# DisplayBoard.net
KiCad netlist of a schematic drawn in EAGLE
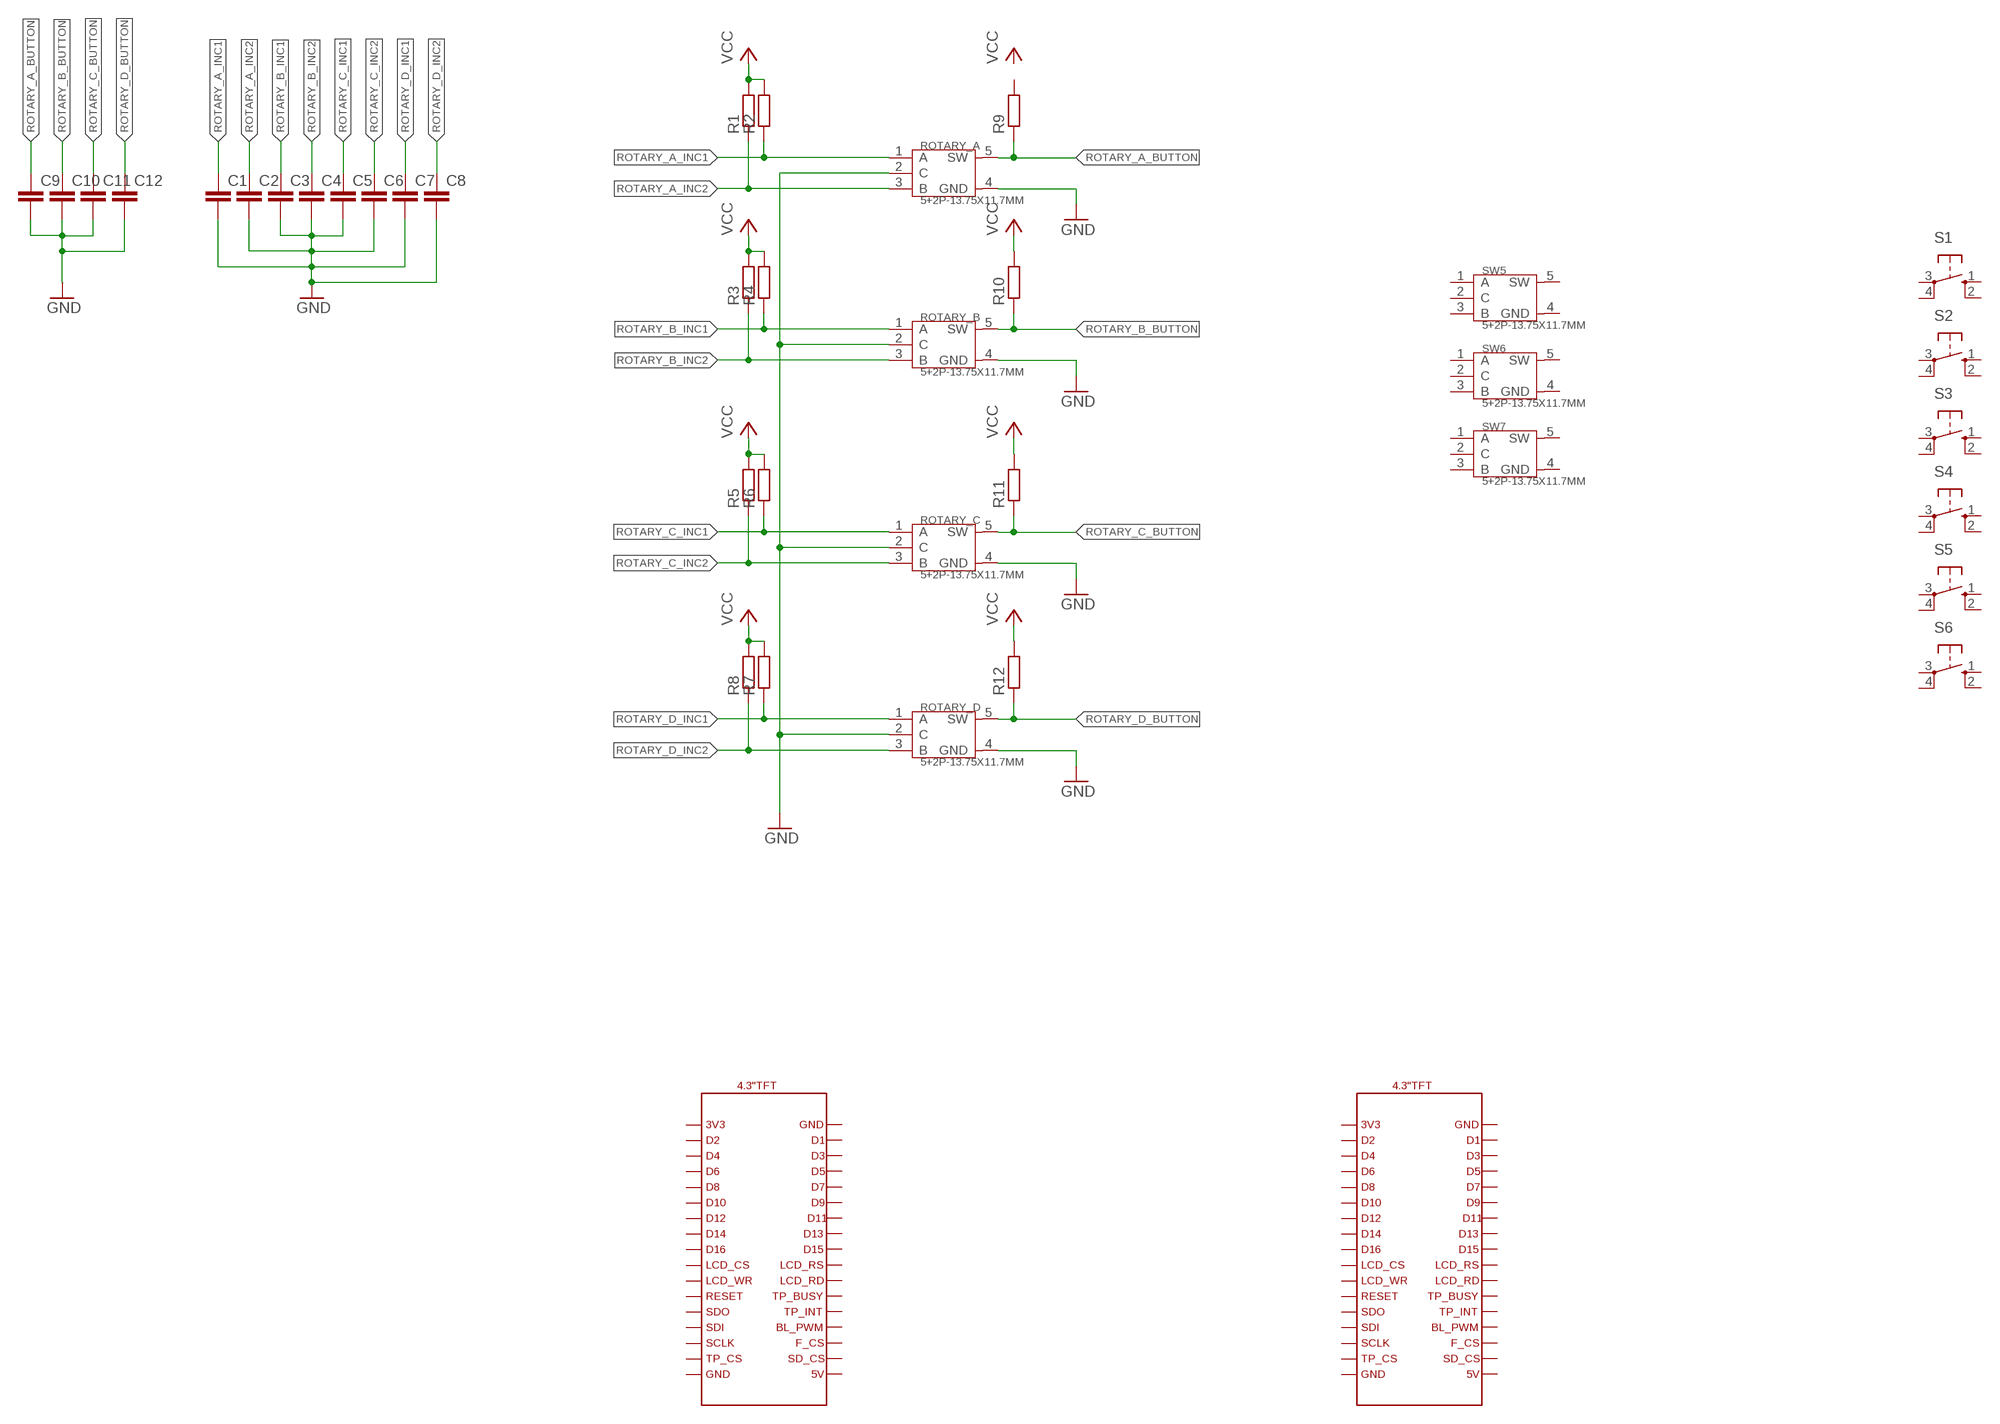
[diagram p0: schematic, sheet 1]

(export (version "E")
  (design (tool "Eeschema 10.0.6"))
  (components
    (comp (ref "C1")
      (value "C-EUC0805")
      (footprint "eagle-import:C0805")
      (libsource (lib "eagle-import") (part "C-EUC0805"))
    )
    (comp (ref "C2")
      (value "C-EUC0805")
      (footprint "eagle-import:C0805")
      (libsource (lib "eagle-import") (part "C-EUC0805"))
    )
    (comp (ref "C3")
      (value "C-EUC0805")
      (footprint "eagle-import:C0805")
      (libsource (lib "eagle-import") (part "C-EUC0805"))
    )
    (comp (ref "C4")
      (value "C-EUC0805")
      (footprint "eagle-import:C0805")
      (libsource (lib "eagle-import") (part "C-EUC0805"))
    )
    (comp (ref "C5")
      (value "C-EUC0805")
      (footprint "eagle-import:C0805")
      (libsource (lib "eagle-import") (part "C-EUC0805"))
    )
    (comp (ref "C6")
      (value "C-EUC0805")
      (footprint "eagle-import:C0805")
      (libsource (lib "eagle-import") (part "C-EUC0805"))
    )
    (comp (ref "C7")
      (value "C-EUC0805")
      (footprint "eagle-import:C0805")
      (libsource (lib "eagle-import") (part "C-EUC0805"))
    )
    (comp (ref "C8")
      (value "C-EUC0805")
      (footprint "eagle-import:C0805")
      (libsource (lib "eagle-import") (part "C-EUC0805"))
    )
    (comp (ref "C9")
      (value "C-EUC0805")
      (footprint "eagle-import:C0805")
      (libsource (lib "eagle-import") (part "C-EUC0805"))
    )
    (comp (ref "C10")
      (value "C-EUC0805")
      (footprint "eagle-import:C0805")
      (libsource (lib "eagle-import") (part "C-EUC0805"))
    )
    (comp (ref "C11")
      (value "C-EUC0805")
      (footprint "eagle-import:C0805")
      (libsource (lib "eagle-import") (part "C-EUC0805"))
    )
    (comp (ref "C12")
      (value "C-EUC0805")
      (footprint "eagle-import:C0805")
      (libsource (lib "eagle-import") (part "C-EUC0805"))
    )
    (comp (ref "R1")
      (value "R-EU_R0805")
      (footprint "eagle-import:R0805")
      (libsource (lib "eagle-import") (part "R-EU_R0805"))
    )
    (comp (ref "R2")
      (value "R-EU_R0805")
      (footprint "eagle-import:R0805")
      (libsource (lib "eagle-import") (part "R-EU_R0805"))
    )
    (comp (ref "R3")
      (value "R-EU_R0805")
      (footprint "eagle-import:R0805")
      (libsource (lib "eagle-import") (part "R-EU_R0805"))
    )
    (comp (ref "R4")
      (value "R-EU_R0805")
      (footprint "eagle-import:R0805")
      (libsource (lib "eagle-import") (part "R-EU_R0805"))
    )
    (comp (ref "R5")
      (value "R-EU_R0805")
      (footprint "eagle-import:R0805")
      (libsource (lib "eagle-import") (part "R-EU_R0805"))
    )
    (comp (ref "R6")
      (value "R-EU_R0805")
      (footprint "eagle-import:R0805")
      (libsource (lib "eagle-import") (part "R-EU_R0805"))
    )
    (comp (ref "R7")
      (value "R-EU_R0805")
      (footprint "eagle-import:R0805")
      (libsource (lib "eagle-import") (part "R-EU_R0805"))
    )
    (comp (ref "R8")
      (value "R-EU_R0805")
      (footprint "eagle-import:R0805")
      (libsource (lib "eagle-import") (part "R-EU_R0805"))
    )
    (comp (ref "R9")
      (value "R-EU_R0805")
      (footprint "eagle-import:R0805")
      (libsource (lib "eagle-import") (part "R-EU_R0805"))
    )
    (comp (ref "R10")
      (value "R-EU_R0805")
      (footprint "eagle-import:R0805")
      (libsource (lib "eagle-import") (part "R-EU_R0805"))
    )
    (comp (ref "R11")
      (value "R-EU_R0805")
      (footprint "eagle-import:R0805")
      (libsource (lib "eagle-import") (part "R-EU_R0805"))
    )
    (comp (ref "R12")
      (value "R-EU_R0805")
      (footprint "eagle-import:R0805")
      (libsource (lib "eagle-import") (part "R-EU_R0805"))
    )
    (comp (ref "ROTARY_A")
      (value "5+2P-13.75X11.7MM")
      (footprint "eagle-import:SW7-13.75X11.7X6.5MM")
      (fields (field (name "MPN") "Rotary-switch"))
      (libsource (lib "eagle-import") (part "DIP-ROTARY-SWITCH(5+2P-13.75X11.7MM)"))
    )
    (comp (ref "ROTARY_B")
      (value "5+2P-13.75X11.7MM")
      (footprint "eagle-import:SW7-13.75X11.7X6.5MM")
      (fields (field (name "MPN") "Rotary-switch"))
      (libsource (lib "eagle-import") (part "DIP-ROTARY-SWITCH(5+2P-13.75X11.7MM)"))
    )
    (comp (ref "ROTARY_C")
      (value "5+2P-13.75X11.7MM")
      (footprint "eagle-import:SW7-13.75X11.7X6.5MM")
      (fields (field (name "MPN") "Rotary-switch"))
      (libsource (lib "eagle-import") (part "DIP-ROTARY-SWITCH(5+2P-13.75X11.7MM)"))
    )
    (comp (ref "ROTARY_D")
      (value "5+2P-13.75X11.7MM")
      (footprint "eagle-import:SW7-13.75X11.7X6.5MM")
      (fields (field (name "MPN") "Rotary-switch"))
      (libsource (lib "eagle-import") (part "DIP-ROTARY-SWITCH(5+2P-13.75X11.7MM)"))
    )
    (comp (ref "S1")
      (value "10-XX")
      (footprint "eagle-import:B3F-10XX")
      (fields (field (name "MPN") "B3F-1000"))
      (libsource (lib "eagle-import") (part "10-XX"))
    )
    (comp (ref "S2")
      (value "10-XX")
      (footprint "eagle-import:B3F-10XX")
      (fields (field (name "MPN") "B3F-1000"))
      (libsource (lib "eagle-import") (part "10-XX"))
    )
    (comp (ref "S3")
      (value "10-XX")
      (footprint "eagle-import:B3F-10XX")
      (fields (field (name "MPN") "B3F-1000"))
      (libsource (lib "eagle-import") (part "10-XX"))
    )
    (comp (ref "S4")
      (value "10-XX")
      (footprint "eagle-import:B3F-10XX")
      (fields (field (name "MPN") "B3F-1000"))
      (libsource (lib "eagle-import") (part "10-XX"))
    )
    (comp (ref "S5")
      (value "10-XX")
      (footprint "eagle-import:B3F-10XX")
      (fields (field (name "MPN") "B3F-1000"))
      (libsource (lib "eagle-import") (part "10-XX"))
    )
    (comp (ref "S6")
      (value "10-XX")
      (footprint "eagle-import:B3F-10XX")
      (fields (field (name "MPN") "B3F-1000"))
      (libsource (lib "eagle-import") (part "10-XX"))
    )
    (comp (ref "SW5")
      (value "5+2P-13.75X11.7MM")
      (footprint "eagle-import:SW7-13.75X11.7X6.5MM")
      (fields (field (name "MPN") "Rotary-switch"))
      (libsource (lib "eagle-import") (part "DIP-ROTARY-SWITCH(5+2P-13.75X11.7MM)"))
    )
    (comp (ref "SW6")
      (value "5+2P-13.75X11.7MM")
      (footprint "eagle-import:SW7-13.75X11.7X6.5MM")
      (fields (field (name "MPN") "Rotary-switch"))
      (libsource (lib "eagle-import") (part "DIP-ROTARY-SWITCH(5+2P-13.75X11.7MM)"))
    )
    (comp (ref "SW7")
      (value "5+2P-13.75X11.7MM")
      (footprint "eagle-import:SW7-13.75X11.7X6.5MM")
      (fields (field (name "MPN") "Rotary-switch"))
      (libsource (lib "eagle-import") (part "DIP-ROTARY-SWITCH(5+2P-13.75X11.7MM)"))
    )
    (comp (ref "U$1")
      (value "4.3\"TFT")
      (footprint "eagle-import:4.3TFT")
      (libsource (lib "eagle-import") (part "4.3{dblquote}TFT"))
    )
  )
  (nets
    (net (code "1") (name "GND") (class "Default")
      (node (ref "C1") (pin "2") (pinfunction "2_2") (pintype "passive"))
      (node (ref "C10") (pin "2") (pinfunction "2_2") (pintype "passive"))
      (node (ref "C11") (pin "2") (pinfunction "2_2") (pintype "passive"))
      (node (ref "C12") (pin "2") (pinfunction "2_2") (pintype "passive"))
      (node (ref "C2") (pin "2") (pinfunction "2_2") (pintype "passive"))
      (node (ref "C3") (pin "2") (pinfunction "2_2") (pintype "passive"))
      (node (ref "C4") (pin "2") (pinfunction "2_2") (pintype "passive"))
      (node (ref "C5") (pin "2") (pinfunction "2_2") (pintype "passive"))
      (node (ref "C6") (pin "2") (pinfunction "2_2") (pintype "passive"))
      (node (ref "C7") (pin "2") (pinfunction "2_2") (pintype "passive"))
      (node (ref "C8") (pin "2") (pinfunction "2_2") (pintype "passive"))
      (node (ref "C9") (pin "2") (pinfunction "2_2") (pintype "passive"))
      (node (ref "ROTARY_A") (pin "2") (pinfunction "C_2") (pintype "bidirectional"))
      (node (ref "ROTARY_A") (pin "4") (pinfunction "GND_4") (pintype "bidirectional"))
      (node (ref "ROTARY_B") (pin "2") (pinfunction "C_2") (pintype "bidirectional"))
      (node (ref "ROTARY_B") (pin "4") (pinfunction "GND_4") (pintype "bidirectional"))
      (node (ref "ROTARY_C") (pin "2") (pinfunction "C_2") (pintype "bidirectional"))
      (node (ref "ROTARY_C") (pin "4") (pinfunction "GND_4") (pintype "bidirectional"))
      (node (ref "ROTARY_D") (pin "2") (pinfunction "C_2") (pintype "bidirectional"))
      (node (ref "ROTARY_D") (pin "4") (pinfunction "GND_4") (pintype "bidirectional"))
    )
    (net (code "2") (name "ROTARY_A_BUTTON") (class "Default")
      (node (ref "C9") (pin "1") (pinfunction "1_1") (pintype "passive"))
      (node (ref "R9") (pin "1") (pinfunction "1_1") (pintype "passive"))
      (node (ref "ROTARY_A") (pin "5") (pinfunction "SW_5") (pintype "bidirectional"))
    )
    (net (code "3") (name "ROTARY_A_INC1") (class "Default")
      (node (ref "C1") (pin "1") (pinfunction "1_1") (pintype "passive"))
      (node (ref "R2") (pin "1") (pinfunction "1_1") (pintype "passive"))
      (node (ref "ROTARY_A") (pin "1") (pinfunction "A_1") (pintype "bidirectional"))
    )
    (net (code "4") (name "ROTARY_A_INC2") (class "Default")
      (node (ref "C2") (pin "1") (pinfunction "1_1") (pintype "passive"))
      (node (ref "R1") (pin "1") (pinfunction "1_1") (pintype "passive"))
      (node (ref "ROTARY_A") (pin "3") (pinfunction "B_3") (pintype "bidirectional"))
    )
    (net (code "5") (name "ROTARY_B_BUTTON") (class "Default")
      (node (ref "C10") (pin "1") (pinfunction "1_1") (pintype "passive"))
      (node (ref "R10") (pin "1") (pinfunction "1_1") (pintype "passive"))
      (node (ref "ROTARY_B") (pin "5") (pinfunction "SW_5") (pintype "bidirectional"))
    )
    (net (code "6") (name "ROTARY_B_INC1") (class "Default")
      (node (ref "C3") (pin "1") (pinfunction "1_1") (pintype "passive"))
      (node (ref "R4") (pin "1") (pinfunction "1_1") (pintype "passive"))
      (node (ref "ROTARY_B") (pin "1") (pinfunction "A_1") (pintype "bidirectional"))
    )
    (net (code "7") (name "ROTARY_B_INC2") (class "Default")
      (node (ref "C4") (pin "1") (pinfunction "1_1") (pintype "passive"))
      (node (ref "R3") (pin "1") (pinfunction "1_1") (pintype "passive"))
      (node (ref "ROTARY_B") (pin "3") (pinfunction "B_3") (pintype "bidirectional"))
    )
    (net (code "8") (name "ROTARY_C_BUTTON") (class "Default")
      (node (ref "C11") (pin "1") (pinfunction "1_1") (pintype "passive"))
      (node (ref "R11") (pin "1") (pinfunction "1_1") (pintype "passive"))
      (node (ref "ROTARY_C") (pin "5") (pinfunction "SW_5") (pintype "bidirectional"))
    )
    (net (code "9") (name "ROTARY_C_INC1") (class "Default")
      (node (ref "C5") (pin "1") (pinfunction "1_1") (pintype "passive"))
      (node (ref "R6") (pin "1") (pinfunction "1_1") (pintype "passive"))
      (node (ref "ROTARY_C") (pin "1") (pinfunction "A_1") (pintype "bidirectional"))
    )
    (net (code "10") (name "ROTARY_C_INC2") (class "Default")
      (node (ref "C6") (pin "1") (pinfunction "1_1") (pintype "passive"))
      (node (ref "R5") (pin "1") (pinfunction "1_1") (pintype "passive"))
      (node (ref "ROTARY_C") (pin "3") (pinfunction "B_3") (pintype "bidirectional"))
    )
    (net (code "11") (name "ROTARY_D_BUTTON") (class "Default")
      (node (ref "C12") (pin "1") (pinfunction "1_1") (pintype "passive"))
      (node (ref "R12") (pin "1") (pinfunction "1_1") (pintype "passive"))
      (node (ref "ROTARY_D") (pin "5") (pinfunction "SW_5") (pintype "bidirectional"))
    )
    (net (code "12") (name "ROTARY_D_INC1") (class "Default")
      (node (ref "C7") (pin "1") (pinfunction "1_1") (pintype "passive"))
      (node (ref "R7") (pin "1") (pinfunction "1_1") (pintype "passive"))
      (node (ref "ROTARY_D") (pin "1") (pinfunction "A_1") (pintype "bidirectional"))
    )
    (net (code "13") (name "ROTARY_D_INC2") (class "Default")
      (node (ref "C8") (pin "1") (pinfunction "1_1") (pintype "passive"))
      (node (ref "R8") (pin "1") (pinfunction "1_1") (pintype "passive"))
      (node (ref "ROTARY_D") (pin "3") (pinfunction "B_3") (pintype "bidirectional"))
    )
    (net (code "14") (name "VCC") (class "Default")
      (node (ref "R1") (pin "2") (pinfunction "2_2") (pintype "passive"))
      (node (ref "R10") (pin "2") (pinfunction "2_2") (pintype "passive"))
      (node (ref "R11") (pin "2") (pinfunction "2_2") (pintype "passive"))
      (node (ref "R12") (pin "2") (pinfunction "2_2") (pintype "passive"))
      (node (ref "R2") (pin "2") (pinfunction "2_2") (pintype "passive"))
      (node (ref "R3") (pin "2") (pinfunction "2_2") (pintype "passive"))
      (node (ref "R4") (pin "2") (pinfunction "2_2") (pintype "passive"))
      (node (ref "R5") (pin "2") (pinfunction "2_2") (pintype "passive"))
      (node (ref "R6") (pin "2") (pinfunction "2_2") (pintype "passive"))
      (node (ref "R7") (pin "2") (pinfunction "2_2") (pintype "passive"))
      (node (ref "R8") (pin "2") (pinfunction "2_2") (pintype "passive"))
    )
    (net (code "15") (name "unconnected-(R9-Pad2)") (class "Default")
      (node (ref "R9") (pin "2") (pinfunction "2_2") (pintype "passive"))
    )
    (net (code "16") (name "unconnected-(S1-P-Pad3)") (class "Default")
      (node (ref "S1") (pin "3") (pinfunction "P_3") (pintype "passive"))
    )
    (net (code "17") (name "unconnected-(S1-P1-Pad4)") (class "Default")
      (node (ref "S1") (pin "4") (pinfunction "P1_4") (pintype "passive"))
    )
    (net (code "18") (name "unconnected-(S1-S-Pad1)") (class "Default")
      (node (ref "S1") (pin "1") (pinfunction "S_1") (pintype "passive"))
    )
    (net (code "19") (name "unconnected-(S1-S1-Pad2)") (class "Default")
      (node (ref "S1") (pin "2") (pinfunction "S1_2") (pintype "passive"))
    )
    (net (code "20") (name "unconnected-(S2-P-Pad3)") (class "Default")
      (node (ref "S2") (pin "3") (pinfunction "P_3") (pintype "passive"))
    )
    (net (code "21") (name "unconnected-(S2-P1-Pad4)") (class "Default")
      (node (ref "S2") (pin "4") (pinfunction "P1_4") (pintype "passive"))
    )
    (net (code "22") (name "unconnected-(S2-S-Pad1)") (class "Default")
      (node (ref "S2") (pin "1") (pinfunction "S_1") (pintype "passive"))
    )
    (net (code "23") (name "unconnected-(S2-S1-Pad2)") (class "Default")
      (node (ref "S2") (pin "2") (pinfunction "S1_2") (pintype "passive"))
    )
    (net (code "24") (name "unconnected-(S3-P-Pad3)") (class "Default")
      (node (ref "S3") (pin "3") (pinfunction "P_3") (pintype "passive"))
    )
    (net (code "25") (name "unconnected-(S3-P1-Pad4)") (class "Default")
      (node (ref "S3") (pin "4") (pinfunction "P1_4") (pintype "passive"))
    )
    (net (code "26") (name "unconnected-(S3-S-Pad1)") (class "Default")
      (node (ref "S3") (pin "1") (pinfunction "S_1") (pintype "passive"))
    )
    (net (code "27") (name "unconnected-(S3-S1-Pad2)") (class "Default")
      (node (ref "S3") (pin "2") (pinfunction "S1_2") (pintype "passive"))
    )
    (net (code "28") (name "unconnected-(S4-P-Pad3)") (class "Default")
      (node (ref "S4") (pin "3") (pinfunction "P_3") (pintype "passive"))
    )
    (net (code "29") (name "unconnected-(S4-P1-Pad4)") (class "Default")
      (node (ref "S4") (pin "4") (pinfunction "P1_4") (pintype "passive"))
    )
    (net (code "30") (name "unconnected-(S4-S-Pad1)") (class "Default")
      (node (ref "S4") (pin "1") (pinfunction "S_1") (pintype "passive"))
    )
    (net (code "31") (name "unconnected-(S4-S1-Pad2)") (class "Default")
      (node (ref "S4") (pin "2") (pinfunction "S1_2") (pintype "passive"))
    )
    (net (code "32") (name "unconnected-(S5-P-Pad3)") (class "Default")
      (node (ref "S5") (pin "3") (pinfunction "P_3") (pintype "passive"))
    )
    (net (code "33") (name "unconnected-(S5-P1-Pad4)") (class "Default")
      (node (ref "S5") (pin "4") (pinfunction "P1_4") (pintype "passive"))
    )
    (net (code "34") (name "unconnected-(S5-S-Pad1)") (class "Default")
      (node (ref "S5") (pin "1") (pinfunction "S_1") (pintype "passive"))
    )
    (net (code "35") (name "unconnected-(S5-S1-Pad2)") (class "Default")
      (node (ref "S5") (pin "2") (pinfunction "S1_2") (pintype "passive"))
    )
    (net (code "36") (name "unconnected-(S6-P-Pad3)") (class "Default")
      (node (ref "S6") (pin "3") (pinfunction "P_3") (pintype "passive"))
    )
    (net (code "37") (name "unconnected-(S6-P1-Pad4)") (class "Default")
      (node (ref "S6") (pin "4") (pinfunction "P1_4") (pintype "passive"))
    )
    (net (code "38") (name "unconnected-(S6-S-Pad1)") (class "Default")
      (node (ref "S6") (pin "1") (pinfunction "S_1") (pintype "passive"))
    )
    (net (code "39") (name "unconnected-(S6-S1-Pad2)") (class "Default")
      (node (ref "S6") (pin "2") (pinfunction "S1_2") (pintype "passive"))
    )
    (net (code "40") (name "unconnected-(SW5-A-Pad1)") (class "Default")
      (node (ref "SW5") (pin "1") (pinfunction "A_1") (pintype "bidirectional"))
    )
    (net (code "41") (name "unconnected-(SW5-B-Pad3)") (class "Default")
      (node (ref "SW5") (pin "3") (pinfunction "B_3") (pintype "bidirectional"))
    )
    (net (code "42") (name "unconnected-(SW5-C-Pad2)") (class "Default")
      (node (ref "SW5") (pin "2") (pinfunction "C_2") (pintype "bidirectional"))
    )
    (net (code "43") (name "unconnected-(SW5-GND-Pad4)") (class "Default")
      (node (ref "SW5") (pin "4") (pinfunction "GND_4") (pintype "bidirectional"))
    )
    (net (code "44") (name "unconnected-(SW5-SW-Pad5)") (class "Default")
      (node (ref "SW5") (pin "5") (pinfunction "SW_5") (pintype "bidirectional"))
    )
    (net (code "45") (name "unconnected-(SW6-A-Pad1)") (class "Default")
      (node (ref "SW6") (pin "1") (pinfunction "A_1") (pintype "bidirectional"))
    )
    (net (code "46") (name "unconnected-(SW6-B-Pad3)") (class "Default")
      (node (ref "SW6") (pin "3") (pinfunction "B_3") (pintype "bidirectional"))
    )
    (net (code "47") (name "unconnected-(SW6-C-Pad2)") (class "Default")
      (node (ref "SW6") (pin "2") (pinfunction "C_2") (pintype "bidirectional"))
    )
    (net (code "48") (name "unconnected-(SW6-GND-Pad4)") (class "Default")
      (node (ref "SW6") (pin "4") (pinfunction "GND_4") (pintype "bidirectional"))
    )
    (net (code "49") (name "unconnected-(SW6-SW-Pad5)") (class "Default")
      (node (ref "SW6") (pin "5") (pinfunction "SW_5") (pintype "bidirectional"))
    )
    (net (code "50") (name "unconnected-(SW7-A-Pad1)") (class "Default")
      (node (ref "SW7") (pin "1") (pinfunction "A_1") (pintype "bidirectional"))
    )
    (net (code "51") (name "unconnected-(SW7-B-Pad3)") (class "Default")
      (node (ref "SW7") (pin "3") (pinfunction "B_3") (pintype "bidirectional"))
    )
    (net (code "52") (name "unconnected-(SW7-C-Pad2)") (class "Default")
      (node (ref "SW7") (pin "2") (pinfunction "C_2") (pintype "bidirectional"))
    )
    (net (code "53") (name "unconnected-(SW7-GND-Pad4)") (class "Default")
      (node (ref "SW7") (pin "4") (pinfunction "GND_4") (pintype "bidirectional"))
    )
    (net (code "54") (name "unconnected-(SW7-SW-Pad5)") (class "Default")
      (node (ref "SW7") (pin "5") (pinfunction "SW_5") (pintype "bidirectional"))
    )
    (net (code "55") (name "unconnected-(U$1A-P$1-PadJP1_1)") (class "Default")
      (node (ref "U$1") (pin "JP1_1") (pinfunction "P$1_JP1_1") (pintype "bidirectional"))
    )
    (net (code "56") (name "unconnected-(U$1A-P$2-PadJP1_2)") (class "Default")
      (node (ref "U$1") (pin "JP1_2") (pinfunction "P$2_JP1_2") (pintype "bidirectional"))
    )
    (net (code "57") (name "unconnected-(U$1A-P$3-PadJP1_3)") (class "Default")
      (node (ref "U$1") (pin "JP1_3") (pinfunction "P$3_JP1_3") (pintype "bidirectional"))
    )
    (net (code "58") (name "unconnected-(U$1A-P$4-PadJP1_4)") (class "Default")
      (node (ref "U$1") (pin "JP1_4") (pinfunction "P$4_JP1_4") (pintype "bidirectional"))
    )
    (net (code "59") (name "unconnected-(U$1A-P$5-PadJP1_5)") (class "Default")
      (node (ref "U$1") (pin "JP1_5") (pinfunction "P$5_JP1_5") (pintype "bidirectional"))
    )
    (net (code "60") (name "unconnected-(U$1A-P$6-PadJP1_6)") (class "Default")
      (node (ref "U$1") (pin "JP1_6") (pinfunction "P$6_JP1_6") (pintype "bidirectional"))
    )
    (net (code "61") (name "unconnected-(U$1A-P$7-PadJP1_7)") (class "Default")
      (node (ref "U$1") (pin "JP1_7") (pinfunction "P$7_JP1_7") (pintype "bidirectional"))
    )
    (net (code "62") (name "unconnected-(U$1A-P$8-PadJP1_8)") (class "Default")
      (node (ref "U$1") (pin "JP1_8") (pinfunction "P$8_JP1_8") (pintype "bidirectional"))
    )
    (net (code "63") (name "unconnected-(U$1A-P$9-PadJP1_9)") (class "Default")
      (node (ref "U$1") (pin "JP1_9") (pinfunction "P$9_JP1_9") (pintype "bidirectional"))
    )
    (net (code "64") (name "unconnected-(U$1A-P$10-PadJP1_10)") (class "Default")
      (node (ref "U$1") (pin "JP1_10") (pinfunction "P$10_JP1_10") (pintype "bidirectional"))
    )
    (net (code "65") (name "unconnected-(U$1A-P$11-PadJP1_11)") (class "Default")
      (node (ref "U$1") (pin "JP1_11") (pinfunction "P$11_JP1_11") (pintype "bidirectional"))
    )
    (net (code "66") (name "unconnected-(U$1A-P$12-PadJP1_12)") (class "Default")
      (node (ref "U$1") (pin "JP1_12") (pinfunction "P$12_JP1_12") (pintype "bidirectional"))
    )
    (net (code "67") (name "unconnected-(U$1A-P$13-PadJP1_13)") (class "Default")
      (node (ref "U$1") (pin "JP1_13") (pinfunction "P$13_JP1_13") (pintype "bidirectional"))
    )
    (net (code "68") (name "unconnected-(U$1A-P$14-PadJP1_14)") (class "Default")
      (node (ref "U$1") (pin "JP1_14") (pinfunction "P$14_JP1_14") (pintype "bidirectional"))
    )
    (net (code "69") (name "unconnected-(U$1A-P$15-PadJP1_15)") (class "Default")
      (node (ref "U$1") (pin "JP1_15") (pinfunction "P$15_JP1_15") (pintype "bidirectional"))
    )
    (net (code "70") (name "unconnected-(U$1A-P$16-PadJP1_16)") (class "Default")
      (node (ref "U$1") (pin "JP1_16") (pinfunction "P$16_JP1_16") (pintype "bidirectional"))
    )
    (net (code "71") (name "unconnected-(U$1A-P$17-PadJP1_17)") (class "Default")
      (node (ref "U$1") (pin "JP1_17") (pinfunction "P$17_JP1_17") (pintype "bidirectional"))
    )
    (net (code "72") (name "unconnected-(U$1A-P$18-PadJP1_18)") (class "Default")
      (node (ref "U$1") (pin "JP1_18") (pinfunction "P$18_JP1_18") (pintype "bidirectional"))
    )
    (net (code "73") (name "unconnected-(U$1A-P$19-PadJP1_19)") (class "Default")
      (node (ref "U$1") (pin "JP1_19") (pinfunction "P$19_JP1_19") (pintype "bidirectional"))
    )
    (net (code "74") (name "unconnected-(U$1A-P$20-PadJP1_20)") (class "Default")
      (node (ref "U$1") (pin "JP1_20") (pinfunction "P$20_JP1_20") (pintype "bidirectional"))
    )
    (net (code "75") (name "unconnected-(U$1A-P$21-PadJP1_21)") (class "Default")
      (node (ref "U$1") (pin "JP1_21") (pinfunction "P$21_JP1_21") (pintype "bidirectional"))
    )
    (net (code "76") (name "unconnected-(U$1A-P$22-PadJP1_22)") (class "Default")
      (node (ref "U$1") (pin "JP1_22") (pinfunction "P$22_JP1_22") (pintype "bidirectional"))
    )
    (net (code "77") (name "unconnected-(U$1A-P$23-PadJP1_23)") (class "Default")
      (node (ref "U$1") (pin "JP1_23") (pinfunction "P$23_JP1_23") (pintype "bidirectional"))
    )
    (net (code "78") (name "unconnected-(U$1A-P$24-PadJP1_24)") (class "Default")
      (node (ref "U$1") (pin "JP1_24") (pinfunction "P$24_JP1_24") (pintype "bidirectional"))
    )
    (net (code "79") (name "unconnected-(U$1A-P$25-PadJP1_25)") (class "Default")
      (node (ref "U$1") (pin "JP1_25") (pinfunction "P$25_JP1_25") (pintype "bidirectional"))
    )
    (net (code "80") (name "unconnected-(U$1A-P$26-PadJP1_26)") (class "Default")
      (node (ref "U$1") (pin "JP1_26") (pinfunction "P$26_JP1_26") (pintype "bidirectional"))
    )
    (net (code "81") (name "unconnected-(U$1A-P$27-PadJP1_27)") (class "Default")
      (node (ref "U$1") (pin "JP1_27") (pinfunction "P$27_JP1_27") (pintype "bidirectional"))
    )
    (net (code "82") (name "unconnected-(U$1A-P$28-PadJP1_28)") (class "Default")
      (node (ref "U$1") (pin "JP1_28") (pinfunction "P$28_JP1_28") (pintype "bidirectional"))
    )
    (net (code "83") (name "unconnected-(U$1A-P$29-PadJP1_29)") (class "Default")
      (node (ref "U$1") (pin "JP1_29") (pinfunction "P$29_JP1_29") (pintype "bidirectional"))
    )
    (net (code "84") (name "unconnected-(U$1A-P$30-PadJP1_30)") (class "Default")
      (node (ref "U$1") (pin "JP1_30") (pinfunction "P$30_JP1_30") (pintype "bidirectional"))
    )
    (net (code "85") (name "unconnected-(U$1A-P$31-PadJP1_31)") (class "Default")
      (node (ref "U$1") (pin "JP1_31") (pinfunction "P$31_JP1_31") (pintype "bidirectional"))
    )
    (net (code "86") (name "unconnected-(U$1A-P$32-PadJP1_32)") (class "Default")
      (node (ref "U$1") (pin "JP1_32") (pinfunction "P$32_JP1_32") (pintype "bidirectional"))
    )
    (net (code "87") (name "unconnected-(U$1A-P$33-PadJP1_33)") (class "Default")
      (node (ref "U$1") (pin "JP1_33") (pinfunction "P$33_JP1_33") (pintype "bidirectional"))
    )
    (net (code "88") (name "unconnected-(U$1A-P$34-PadJP1_34)") (class "Default")
      (node (ref "U$1") (pin "JP1_34") (pinfunction "P$34_JP1_34") (pintype "bidirectional"))
    )
    (net (code "89") (name "unconnected-(U$1B-P$1-PadJP2_1)") (class "Default")
      (node (ref "U$1") (pin "JP2_1") (pinfunction "P$1_JP2_1") (pintype "bidirectional"))
    )
    (net (code "90") (name "unconnected-(U$1B-P$2-PadJP2_2)") (class "Default")
      (node (ref "U$1") (pin "JP2_2") (pinfunction "P$2_JP2_2") (pintype "bidirectional"))
    )
    (net (code "91") (name "unconnected-(U$1B-P$3-PadJP2_3)") (class "Default")
      (node (ref "U$1") (pin "JP2_3") (pinfunction "P$3_JP2_3") (pintype "bidirectional"))
    )
    (net (code "92") (name "unconnected-(U$1B-P$4-PadJP2_4)") (class "Default")
      (node (ref "U$1") (pin "JP2_4") (pinfunction "P$4_JP2_4") (pintype "bidirectional"))
    )
    (net (code "93") (name "unconnected-(U$1B-P$5-PadJP2_5)") (class "Default")
      (node (ref "U$1") (pin "JP2_5") (pinfunction "P$5_JP2_5") (pintype "bidirectional"))
    )
    (net (code "94") (name "unconnected-(U$1B-P$6-PadJP2_6)") (class "Default")
      (node (ref "U$1") (pin "JP2_6") (pinfunction "P$6_JP2_6") (pintype "bidirectional"))
    )
    (net (code "95") (name "unconnected-(U$1B-P$7-PadJP2_7)") (class "Default")
      (node (ref "U$1") (pin "JP2_7") (pinfunction "P$7_JP2_7") (pintype "bidirectional"))
    )
    (net (code "96") (name "unconnected-(U$1B-P$8-PadJP2_8)") (class "Default")
      (node (ref "U$1") (pin "JP2_8") (pinfunction "P$8_JP2_8") (pintype "bidirectional"))
    )
    (net (code "97") (name "unconnected-(U$1B-P$9-PadJP2_9)") (class "Default")
      (node (ref "U$1") (pin "JP2_9") (pinfunction "P$9_JP2_9") (pintype "bidirectional"))
    )
    (net (code "98") (name "unconnected-(U$1B-P$10-PadJP2_10)") (class "Default")
      (node (ref "U$1") (pin "JP2_10") (pinfunction "P$10_JP2_10") (pintype "bidirectional"))
    )
    (net (code "99") (name "unconnected-(U$1B-P$11-PadJP2_11)") (class "Default")
      (node (ref "U$1") (pin "JP2_11") (pinfunction "P$11_JP2_11") (pintype "bidirectional"))
    )
    (net (code "100") (name "unconnected-(U$1B-P$12-PadJP2_12)") (class "Default")
      (node (ref "U$1") (pin "JP2_12") (pinfunction "P$12_JP2_12") (pintype "bidirectional"))
    )
    (net (code "101") (name "unconnected-(U$1B-P$13-PadJP2_13)") (class "Default")
      (node (ref "U$1") (pin "JP2_13") (pinfunction "P$13_JP2_13") (pintype "bidirectional"))
    )
    (net (code "102") (name "unconnected-(U$1B-P$14-PadJP2_14)") (class "Default")
      (node (ref "U$1") (pin "JP2_14") (pinfunction "P$14_JP2_14") (pintype "bidirectional"))
    )
    (net (code "103") (name "unconnected-(U$1B-P$15-PadJP2_15)") (class "Default")
      (node (ref "U$1") (pin "JP2_15") (pinfunction "P$15_JP2_15") (pintype "bidirectional"))
    )
    (net (code "104") (name "unconnected-(U$1B-P$16-PadJP2_16)") (class "Default")
      (node (ref "U$1") (pin "JP2_16") (pinfunction "P$16_JP2_16") (pintype "bidirectional"))
    )
    (net (code "105") (name "unconnected-(U$1B-P$17-PadJP2_17)") (class "Default")
      (node (ref "U$1") (pin "JP2_17") (pinfunction "P$17_JP2_17") (pintype "bidirectional"))
    )
    (net (code "106") (name "unconnected-(U$1B-P$18-PadJP2_18)") (class "Default")
      (node (ref "U$1") (pin "JP2_18") (pinfunction "P$18_JP2_18") (pintype "bidirectional"))
    )
    (net (code "107") (name "unconnected-(U$1B-P$19-PadJP2_19)") (class "Default")
      (node (ref "U$1") (pin "JP2_19") (pinfunction "P$19_JP2_19") (pintype "bidirectional"))
    )
    (net (code "108") (name "unconnected-(U$1B-P$20-PadJP2_20)") (class "Default")
      (node (ref "U$1") (pin "JP2_20") (pinfunction "P$20_JP2_20") (pintype "bidirectional"))
    )
    (net (code "109") (name "unconnected-(U$1B-P$21-PadJP2_21)") (class "Default")
      (node (ref "U$1") (pin "JP2_21") (pinfunction "P$21_JP2_21") (pintype "bidirectional"))
    )
    (net (code "110") (name "unconnected-(U$1B-P$22-PadJP2_22)") (class "Default")
      (node (ref "U$1") (pin "JP2_22") (pinfunction "P$22_JP2_22") (pintype "bidirectional"))
    )
    (net (code "111") (name "unconnected-(U$1B-P$23-PadJP2_23)") (class "Default")
      (node (ref "U$1") (pin "JP2_23") (pinfunction "P$23_JP2_23") (pintype "bidirectional"))
    )
    (net (code "112") (name "unconnected-(U$1B-P$24-PadJP2_24)") (class "Default")
      (node (ref "U$1") (pin "JP2_24") (pinfunction "P$24_JP2_24") (pintype "bidirectional"))
    )
    (net (code "113") (name "unconnected-(U$1B-P$25-PadJP2_25)") (class "Default")
      (node (ref "U$1") (pin "JP2_25") (pinfunction "P$25_JP2_25") (pintype "bidirectional"))
    )
    (net (code "114") (name "unconnected-(U$1B-P$26-PadJP2_26)") (class "Default")
      (node (ref "U$1") (pin "JP2_26") (pinfunction "P$26_JP2_26") (pintype "bidirectional"))
    )
    (net (code "115") (name "unconnected-(U$1B-P$27-PadJP2_27)") (class "Default")
      (node (ref "U$1") (pin "JP2_27") (pinfunction "P$27_JP2_27") (pintype "bidirectional"))
    )
    (net (code "116") (name "unconnected-(U$1B-P$28-PadJP2_28)") (class "Default")
      (node (ref "U$1") (pin "JP2_28") (pinfunction "P$28_JP2_28") (pintype "bidirectional"))
    )
    (net (code "117") (name "unconnected-(U$1B-P$29-PadJP2_29)") (class "Default")
      (node (ref "U$1") (pin "JP2_29") (pinfunction "P$29_JP2_29") (pintype "bidirectional"))
    )
    (net (code "118") (name "unconnected-(U$1B-P$30-PadJP2_30)") (class "Default")
      (node (ref "U$1") (pin "JP2_30") (pinfunction "P$30_JP2_30") (pintype "bidirectional"))
    )
    (net (code "119") (name "unconnected-(U$1B-P$31-PadJP2_31)") (class "Default")
      (node (ref "U$1") (pin "JP2_31") (pinfunction "P$31_JP2_31") (pintype "bidirectional"))
    )
    (net (code "120") (name "unconnected-(U$1B-P$32-PadJP2_32)") (class "Default")
      (node (ref "U$1") (pin "JP2_32") (pinfunction "P$32_JP2_32") (pintype "bidirectional"))
    )
    (net (code "121") (name "unconnected-(U$1B-P$33-PadJP2_33)") (class "Default")
      (node (ref "U$1") (pin "JP2_33") (pinfunction "P$33_JP2_33") (pintype "bidirectional"))
    )
    (net (code "122") (name "unconnected-(U$1B-P$34-PadJP2_34)") (class "Default")
      (node (ref "U$1") (pin "JP2_34") (pinfunction "P$34_JP2_34") (pintype "bidirectional"))
    )
  )
)
